# AMP.net
KiCad netlist of a schematic drawn in Altium Designer
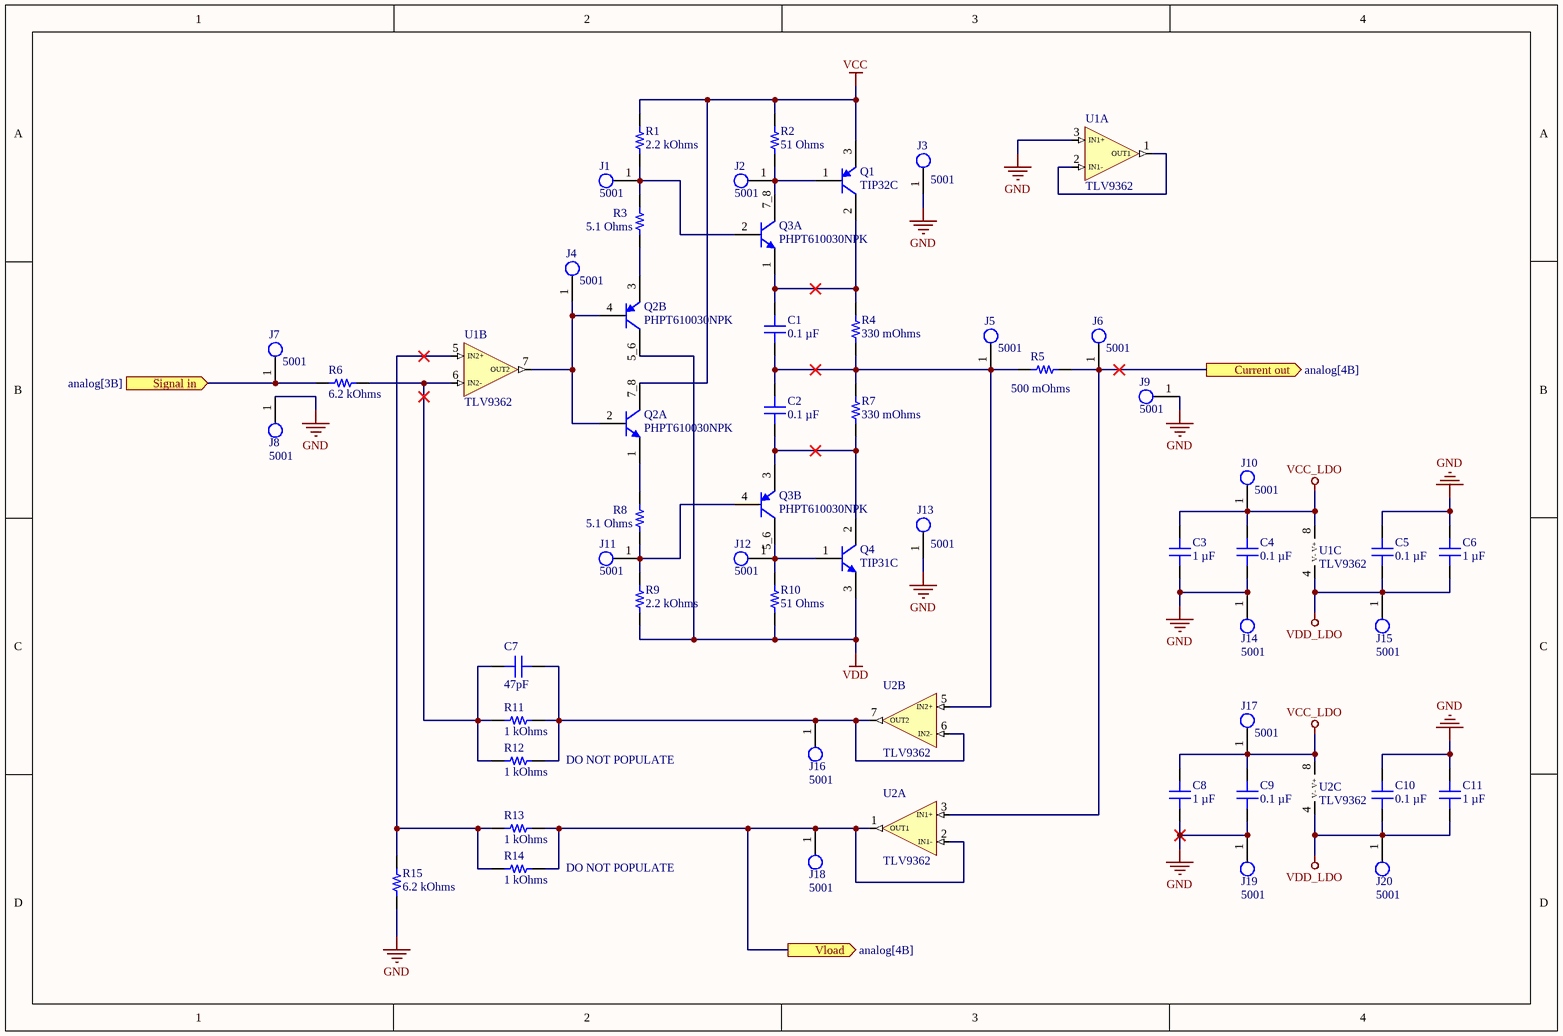
[diagram p0: AMP.SchDoc]

(export (version "E")
  (design (tool "Eeschema 10.0.6"))
  (components
    (comp (ref "C1")
      (value "0.1 µF")
      (footprint "CAP 1206_3216 - 0.8MM")
      (description "CAP CER 0.1UF 50V X7R 1206")
      (fields
        (field (name "PART NUMBER") "885012208087")
        (field (name "CAPACITANCE") "0.1 µF")
        (field (name "MANUFACTURER") "Würth Elektronik")
      )
      (libsource (lib "Celestial Altium Library - altium_library") (part "Capacitor"))
    )
    (comp (ref "C2")
      (value "0.1 µF")
      (footprint "CAP 1206_3216 - 0.8MM")
      (description "CAP CER 0.1UF 50V X7R 1206")
      (fields
        (field (name "PART NUMBER") "885012208087")
        (field (name "CAPACITANCE") "0.1 µF")
        (field (name "MANUFACTURER") "Würth Elektronik")
      )
      (libsource (lib "Celestial Altium Library - altium_library") (part "Capacitor"))
    )
    (comp (ref "C3")
      (value "1 µF")
      (footprint "CAP 1206_3216 - 0.8MM")
      (description "CAP CER 1UF 50V X7R 1206")
      (fields
        (field (name "PART NUMBER") "885012208093")
        (field (name "CAPACITANCE") "1 µF")
        (field (name "MANUFACTURER") "Würth Elektronik")
      )
      (libsource (lib "Celestial Altium Library - altium_library") (part "Capacitor"))
    )
    (comp (ref "C4")
      (value "0.1 µF")
      (footprint "CAP 1206_3216 - 0.8MM")
      (description "CAP CER 0.1UF 50V X7R 1206")
      (fields
        (field (name "PART NUMBER") "885012208087")
        (field (name "CAPACITANCE") "0.1 µF")
        (field (name "MANUFACTURER") "Würth Elektronik")
      )
      (libsource (lib "Celestial Altium Library - altium_library") (part "Capacitor"))
    )
    (comp (ref "C5")
      (value "0.1 µF")
      (footprint "CAP 1206_3216 - 0.8MM")
      (description "CAP CER 0.1UF 50V X7R 1206")
      (fields
        (field (name "PART NUMBER") "885012208087")
        (field (name "CAPACITANCE") "0.1 µF")
        (field (name "MANUFACTURER") "Würth Elektronik")
      )
      (libsource (lib "Celestial Altium Library - altium_library") (part "Capacitor"))
    )
    (comp (ref "C6")
      (value "1 µF")
      (footprint "CAP 1206_3216 - 0.8MM")
      (description "CAP CER 1UF 50V X7R 1206")
      (fields
        (field (name "PART NUMBER") "885012208093")
        (field (name "CAPACITANCE") "1 µF")
        (field (name "MANUFACTURER") "Würth Elektronik")
      )
      (libsource (lib "Celestial Altium Library - altium_library") (part "Capacitor"))
    )
    (comp (ref "C7")
      (value "47pF")
      (footprint "CAP 1206_3216 - 1.8MM")
      (description "CAP CER 47PF 1KV C0G/NP0 1206")
      (fields
        (field (name "PART NUMBER") "1206AA470KAT1A")
        (field (name "CAPACITANCE") "47pF")
        (field (name "MANUFACTURER") "AVX Corporation")
      )
      (libsource (lib "Celestial Altium Library - altium_library") (part "Capacitor"))
    )
    (comp (ref "C8")
      (value "1 µF")
      (footprint "CAP 1206_3216 - 0.8MM")
      (description "CAP CER 1UF 50V X7R 1206")
      (fields
        (field (name "PART NUMBER") "885012208093")
        (field (name "CAPACITANCE") "1 µF")
        (field (name "MANUFACTURER") "Würth Elektronik")
      )
      (libsource (lib "Celestial Altium Library - altium_library") (part "Capacitor"))
    )
    (comp (ref "C9")
      (value "0.1 µF")
      (footprint "CAP 1206_3216 - 0.8MM")
      (description "CAP CER 0.1UF 50V X7R 1206")
      (fields
        (field (name "PART NUMBER") "885012208087")
        (field (name "CAPACITANCE") "0.1 µF")
        (field (name "MANUFACTURER") "Würth Elektronik")
      )
      (libsource (lib "Celestial Altium Library - altium_library") (part "Capacitor"))
    )
    (comp (ref "C10")
      (value "0.1 µF")
      (footprint "CAP 1206_3216 - 0.8MM")
      (description "CAP CER 0.1UF 50V X7R 1206")
      (fields
        (field (name "PART NUMBER") "885012208087")
        (field (name "CAPACITANCE") "0.1 µF")
        (field (name "MANUFACTURER") "Würth Elektronik")
      )
      (libsource (lib "Celestial Altium Library - altium_library") (part "Capacitor"))
    )
    (comp (ref "C11")
      (value "1 µF")
      (footprint "CAP 1206_3216 - 0.8MM")
      (description "CAP CER 1UF 50V X7R 1206")
      (fields
        (field (name "PART NUMBER") "885012208093")
        (field (name "CAPACITANCE") "1 µF")
        (field (name "MANUFACTURER") "Würth Elektronik")
      )
      (libsource (lib "Celestial Altium Library - altium_library") (part "Capacitor"))
    )
    (comp (ref "J1")
      (value "5001")
      (footprint "FP-5001-MFG")
      (description "PC TEST POINT MINIATURE BLACK")
      (libsource (lib "za_koncar") (part "CMP-2000-05181-2"))
    )
    (comp (ref "J2")
      (value "5001")
      (footprint "FP-5001-MFG")
      (description "PC TEST POINT MINIATURE BLACK")
      (libsource (lib "za_koncar") (part "CMP-2000-05181-2"))
    )
    (comp (ref "J3")
      (value "5001")
      (footprint "FP-5001-MFG")
      (description "PC TEST POINT MINIATURE BLACK")
      (libsource (lib "za_koncar") (part "CMP-2000-05181-2"))
    )
    (comp (ref "J4")
      (value "5001")
      (footprint "FP-5001-MFG")
      (description "PC TEST POINT MINIATURE BLACK")
      (libsource (lib "za_koncar") (part "CMP-2000-05181-2"))
    )
    (comp (ref "J5")
      (value "5001")
      (footprint "FP-5001-MFG")
      (description "PC TEST POINT MINIATURE BLACK")
      (libsource (lib "za_koncar") (part "CMP-2000-05181-2"))
    )
    (comp (ref "J6")
      (value "5001")
      (footprint "FP-5001-MFG")
      (description "PC TEST POINT MINIATURE BLACK")
      (libsource (lib "za_koncar") (part "CMP-2000-05181-2"))
    )
    (comp (ref "J7")
      (value "5001")
      (footprint "FP-5001-MFG")
      (description "PC TEST POINT MINIATURE BLACK")
      (libsource (lib "za_koncar") (part "CMP-2000-05181-2"))
    )
    (comp (ref "J8")
      (value "5001")
      (footprint "FP-5001-MFG")
      (description "PC TEST POINT MINIATURE BLACK")
      (libsource (lib "za_koncar") (part "CMP-2000-05181-2"))
    )
    (comp (ref "J9")
      (value "5001")
      (footprint "FP-5001-MFG")
      (description "PC TEST POINT MINIATURE BLACK")
      (libsource (lib "za_koncar") (part "CMP-2000-05181-2"))
    )
    (comp (ref "J10")
      (value "5001")
      (footprint "FP-5001-MFG")
      (description "PC TEST POINT MINIATURE BLACK")
      (libsource (lib "za_koncar") (part "CMP-2000-05181-2"))
    )
    (comp (ref "J11")
      (value "5001")
      (footprint "FP-5001-MFG")
      (description "PC TEST POINT MINIATURE BLACK")
      (libsource (lib "za_koncar") (part "CMP-2000-05181-2"))
    )
    (comp (ref "J12")
      (value "5001")
      (footprint "FP-5001-MFG")
      (description "PC TEST POINT MINIATURE BLACK")
      (libsource (lib "za_koncar") (part "CMP-2000-05181-2"))
    )
    (comp (ref "J13")
      (value "5001")
      (footprint "FP-5001-MFG")
      (description "PC TEST POINT MINIATURE BLACK")
      (libsource (lib "za_koncar") (part "CMP-2000-05181-2"))
    )
    (comp (ref "J14")
      (value "5001")
      (footprint "FP-5001-MFG")
      (description "PC TEST POINT MINIATURE BLACK")
      (libsource (lib "za_koncar") (part "CMP-2000-05181-2"))
    )
    (comp (ref "J15")
      (value "5001")
      (footprint "FP-5001-MFG")
      (description "PC TEST POINT MINIATURE BLACK")
      (libsource (lib "za_koncar") (part "CMP-2000-05181-2"))
    )
    (comp (ref "J16")
      (value "5001")
      (footprint "FP-5001-MFG")
      (description "PC TEST POINT MINIATURE BLACK")
      (libsource (lib "za_koncar") (part "CMP-2000-05181-2"))
    )
    (comp (ref "J17")
      (value "5001")
      (footprint "FP-5001-MFG")
      (description "PC TEST POINT MINIATURE BLACK")
      (libsource (lib "za_koncar") (part "CMP-2000-05181-2"))
    )
    (comp (ref "J18")
      (value "5001")
      (footprint "FP-5001-MFG")
      (description "PC TEST POINT MINIATURE BLACK")
      (libsource (lib "za_koncar") (part "CMP-2000-05181-2"))
    )
    (comp (ref "J19")
      (value "5001")
      (footprint "FP-5001-MFG")
      (description "PC TEST POINT MINIATURE BLACK")
      (libsource (lib "za_koncar") (part "CMP-2000-05181-2"))
    )
    (comp (ref "J20")
      (value "5001")
      (footprint "FP-5001-MFG")
      (description "PC TEST POINT MINIATURE BLACK")
      (libsource (lib "za_koncar") (part "CMP-2000-05181-2"))
    )
    (comp (ref "Q1")
      (value "TIP32C")
      (footprint "ONSC-TO-220-3-221A-09")
      (description "Complementary Silicon Plastic Power Transistor, 3-Pin TO-220, Tube")
      (fields (field (name "MANUFACTURER") "On Semiconductor"))
      (libsource (lib "ON Semi General Purpose Transistors") (part "TIP32C"))
    )
    (comp (ref "Q2")
      (value "PHPT610030NPK")
      (footprint "TRANS_BUK9K18-40E,115")
      (libsource (lib "za_koncar") (part "PHPT610030NPK"))
    )
    (comp (ref "Q3")
      (value "PHPT610030NPK")
      (footprint "TRANS_BUK9K18-40E,115")
      (libsource (lib "za_koncar") (part "PHPT610030NPK"))
    )
    (comp (ref "Q4")
      (value "TIP31C")
      (footprint "ONSC-TO-220-3-221A-09")
      (description "Complementary Silicon Plastic Power Transistor, 3-Pin TO-220, Tube")
      (fields (field (name "MANUFACTURER") "On Semiconductor"))
      (libsource (lib "ON Semi General Purpose Transistors") (part "TIP31C"))
    )
    (comp (ref "R1")
      (value "2.2 kOhms")
      (footprint "RES 1206_3216")
      (description "RES SMD 2.2K OHM 5% 1/4W 1206")
      (fields
        (field (name "PART NUMBER") "ERJ-8GEYJ222V")
        (field (name "MANUFACTURER") "Panasonic Electronic Components")
      )
      (libsource (lib "Celestial Altium Library - altium_library") (part "Resistor"))
    )
    (comp (ref "R2")
      (value "51 Ohms")
      (footprint "RES 1206_3216")
      (description "RES SMD 51 OHM 5% 1/4W 1206")
      (fields
        (field (name "PART NUMBER") "ERJ-8GEYJ510V")
        (field (name "MANUFACTURER") "Panasonic Electronic Components")
      )
      (libsource (lib "Celestial Altium Library - altium_library") (part "Resistor"))
    )
    (comp (ref "R3")
      (value "5.1 Ohms")
      (footprint "RES 1206_3216")
      (description "RES SMD 5.1 OHM 5% 1/4W 1206")
      (fields
        (field (name "PART NUMBER") "ERJ-8GEYJ5R1V")
        (field (name "MANUFACTURER") "Panasonic Electronic Components")
      )
      (libsource (lib "Celestial Altium Library - altium_library") (part "Resistor"))
    )
    (comp (ref "R4")
      (value "330 mOhms")
      (footprint "STACKPOLE CSR2512")
      (description "RES 0.33 OHM 1% 2W 2512")
      (fields
        (field (name "PART NUMBER") "CSRN2512FKR330")
        (field (name "MANUFACTURER") "Stackpole Electronics Inc")
      )
      (libsource (lib "Celestial Altium Library - altium_library") (part "Resistor"))
    )
    (comp (ref "R5")
      (value "500 mOhms")
      (footprint "STACKPOLE CSR2512")
      (description "RES 0.5 OHM 1% 2W 2512")
      (fields
        (field (name "PART NUMBER") "CSRN2512FKR500")
        (field (name "MANUFACTURER") "Stackpole Electronics Inc")
      )
      (libsource (lib "Celestial Altium Library - altium_library") (part "Resistor"))
    )
    (comp (ref "R6")
      (value "6.2 kOhms")
      (footprint "RES 1206_3216")
      (description "RES SMD 6.2K OHM 0.1% 1/4W 1206")
      (fields
        (field (name "PART NUMBER") "ERA-8AEB622V")
        (field (name "MANUFACTURER") "Panasonic Electronic Components")
      )
      (libsource (lib "Celestial Altium Library - altium_library") (part "Resistor"))
    )
    (comp (ref "R7")
      (value "330 mOhms")
      (footprint "STACKPOLE CSR2512")
      (description "RES 0.33 OHM 1% 2W 2512")
      (fields
        (field (name "PART NUMBER") "CSRN2512FKR330")
        (field (name "MANUFACTURER") "Stackpole Electronics Inc")
      )
      (libsource (lib "Celestial Altium Library - altium_library") (part "Resistor"))
    )
    (comp (ref "R8")
      (value "5.1 Ohms")
      (footprint "RES 1206_3216")
      (description "RES SMD 5.1 OHM 5% 1/4W 1206")
      (fields
        (field (name "PART NUMBER") "ERJ-8GEYJ5R1V")
        (field (name "MANUFACTURER") "Panasonic Electronic Components")
      )
      (libsource (lib "Celestial Altium Library - altium_library") (part "Resistor"))
    )
    (comp (ref "R9")
      (value "2.2 kOhms")
      (footprint "RES 1206_3216")
      (description "RES SMD 2.2K OHM 5% 1/4W 1206")
      (fields
        (field (name "PART NUMBER") "ERJ-8GEYJ222V")
        (field (name "MANUFACTURER") "Panasonic Electronic Components")
      )
      (libsource (lib "Celestial Altium Library - altium_library") (part "Resistor"))
    )
    (comp (ref "R10")
      (value "51 Ohms")
      (footprint "RES 1206_3216")
      (description "RES SMD 51 OHM 5% 1/4W 1206")
      (fields
        (field (name "PART NUMBER") "ERJ-8GEYJ510V")
        (field (name "MANUFACTURER") "Panasonic Electronic Components")
      )
      (libsource (lib "Celestial Altium Library - altium_library") (part "Resistor"))
    )
    (comp (ref "R11")
      (value "1 kOhms")
      (footprint "RES 1206_3216")
      (description "RES SMD 1K OHM 0.1% 1/4W 1206")
      (fields
        (field (name "PART NUMBER") "ERA-8AEB102V")
        (field (name "MANUFACTURER") "Panasonic Electronic Components")
      )
      (libsource (lib "Celestial Altium Library - altium_library") (part "Resistor"))
    )
    (comp (ref "R12")
      (value "1 kOhms")
      (footprint "RES 1206_3216")
      (description "RES SMD 1K OHM 0.1% 1/4W 1206")
      (fields
        (field (name "PART NUMBER") "ERA-8AEB102V")
        (field (name "MANUFACTURER") "Panasonic Electronic Components")
      )
      (libsource (lib "Celestial Altium Library - altium_library") (part "Resistor"))
    )
    (comp (ref "R13")
      (value "1 kOhms")
      (footprint "RES 1206_3216")
      (description "RES SMD 1K OHM 0.1% 1/4W 1206")
      (fields
        (field (name "PART NUMBER") "ERA-8AEB102V")
        (field (name "MANUFACTURER") "Panasonic Electronic Components")
      )
      (libsource (lib "Celestial Altium Library - altium_library") (part "Resistor"))
    )
    (comp (ref "R14")
      (value "1 kOhms")
      (footprint "RES 1206_3216")
      (description "RES SMD 1K OHM 0.1% 1/4W 1206")
      (fields
        (field (name "PART NUMBER") "ERA-8AEB102V")
        (field (name "MANUFACTURER") "Panasonic Electronic Components")
      )
      (libsource (lib "Celestial Altium Library - altium_library") (part "Resistor"))
    )
    (comp (ref "R15")
      (value "6.2 kOhms")
      (footprint "RES 1206_3216")
      (description "RES SMD 6.2K OHM 0.1% 1/4W 1206")
      (fields
        (field (name "PART NUMBER") "ERA-8AEB622V")
        (field (name "MANUFACTURER") "Panasonic Electronic Components")
      )
      (libsource (lib "Celestial Altium Library - altium_library") (part "Resistor"))
    )
    (comp (ref "U1")
      (value "TLV9362")
      (footprint "za_koncar:SOIC8-127P600X175-8N")
      (description "TLV936x 10-MHz, 40-V, RRO, Operational Amplifie")
      (libsource (lib "za_koncar") (part "TLV9362"))
    )
    (comp (ref "U2")
      (value "TLV9362")
      (footprint "za_koncar:SOIC8-127P600X175-8N")
      (description "TLV936x 10-MHz, 40-V, RRO, Operational Amplifie")
      (libsource (lib "za_koncar") (part "TLV9362"))
    )
  )
  (nets
    (net (code "1") (name "/Current out") (class "Default")
      (node (ref "J6") (pin "1") (pinfunction "1_1") (pintype "passive"))
      (node (ref "R5") (pin "1") (pinfunction "1_1") (pintype "passive"))
      (node (ref "U2") (pin "3") (pinfunction "IN1+_3") (pintype "input"))
    )
    (net (code "2") (name "/Signal in") (class "Default")
      (node (ref "J7") (pin "1") (pinfunction "1_1") (pintype "passive"))
      (node (ref "R6") (pin "2") (pinfunction "2_2") (pintype "passive"))
    )
    (net (code "3") (name "/Vload") (class "Default")
      (node (ref "J18") (pin "1") (pinfunction "1_1") (pintype "passive"))
      (node (ref "R13") (pin "2") (pinfunction "2_2") (pintype "passive"))
      (node (ref "R14") (pin "2") (pinfunction "2_2") (pintype "passive"))
      (node (ref "U2") (pin "1") (pinfunction "OUT1_1") (pintype "output"))
      (node (ref "U2") (pin "2") (pinfunction "IN1-_2") (pintype "input"))
    )
    (net (code "4") (name "GND") (class "Default")
      (node (ref "C10") (pin "2") (pinfunction "2_2") (pintype "passive"))
      (node (ref "C11") (pin "2") (pinfunction "2_2") (pintype "passive"))
      (node (ref "C3") (pin "1") (pinfunction "1_1") (pintype "passive"))
      (node (ref "C4") (pin "1") (pinfunction "1_1") (pintype "passive"))
      (node (ref "C5") (pin "2") (pinfunction "2_2") (pintype "passive"))
      (node (ref "C6") (pin "2") (pinfunction "2_2") (pintype "passive"))
      (node (ref "C8") (pin "1") (pinfunction "1_1") (pintype "passive"))
      (node (ref "C9") (pin "1") (pinfunction "1_1") (pintype "passive"))
      (node (ref "J13") (pin "1") (pinfunction "1_1") (pintype "passive"))
      (node (ref "J14") (pin "1") (pinfunction "1_1") (pintype "passive"))
      (node (ref "J19") (pin "1") (pinfunction "1_1") (pintype "passive"))
      (node (ref "J3") (pin "1") (pinfunction "1_1") (pintype "passive"))
      (node (ref "J8") (pin "1") (pinfunction "1_1") (pintype "passive"))
      (node (ref "J9") (pin "1") (pinfunction "1_1") (pintype "passive"))
      (node (ref "R15") (pin "1") (pinfunction "1_1") (pintype "passive"))
      (node (ref "U1") (pin "3") (pinfunction "IN1+_3") (pintype "input"))
    )
    (net (code "5") (name "Net-(Q1-B)") (class "Default")
      (node (ref "J2") (pin "1") (pinfunction "1_1") (pintype "passive"))
      (node (ref "Q1") (pin "1") (pinfunction "B_1") (pintype "passive"))
      (node (ref "Q3") (pin "7_8") (pinfunction "C1_7_8") (pintype "passive"))
      (node (ref "R2") (pin "1") (pinfunction "1_1") (pintype "passive"))
    )
    (net (code "6") (name "Net-(Q1-C)") (class "Default")
      (node (ref "C1") (pin "2") (pinfunction "2_2") (pintype "passive"))
      (node (ref "Q1") (pin "2") (pinfunction "C_2") (pintype "passive"))
      (node (ref "Q3") (pin "1") (pinfunction "E1_1") (pintype "passive"))
      (node (ref "R4") (pin "2") (pinfunction "2_2") (pintype "passive"))
    )
    (net (code "7") (name "Net-(Q2A-B1)") (class "Default")
      (node (ref "J4") (pin "1") (pinfunction "1_1") (pintype "passive"))
      (node (ref "Q2") (pin "2") (pinfunction "B1_2") (pintype "passive"))
      (node (ref "Q2") (pin "4") (pinfunction "B2_4") (pintype "passive"))
      (node (ref "U1") (pin "7") (pinfunction "OUT2_7") (pintype "output"))
    )
    (net (code "8") (name "Net-(Q2A-E1)") (class "Default")
      (node (ref "Q2") (pin "1") (pinfunction "E1_1") (pintype "passive"))
      (node (ref "R8") (pin "2") (pinfunction "2_2") (pintype "passive"))
    )
    (net (code "9") (name "Net-(Q2B-E2)") (class "Default")
      (node (ref "Q2") (pin "3") (pinfunction "E2_3") (pintype "passive"))
      (node (ref "R3") (pin "1") (pinfunction "1_1") (pintype "passive"))
    )
    (net (code "10") (name "Net-(Q3A-B1)") (class "Default")
      (node (ref "J1") (pin "1") (pinfunction "1_1") (pintype "passive"))
      (node (ref "Q3") (pin "2") (pinfunction "B1_2") (pintype "passive"))
      (node (ref "R1") (pin "1") (pinfunction "1_1") (pintype "passive"))
      (node (ref "R3") (pin "2") (pinfunction "2_2") (pintype "passive"))
    )
    (net (code "11") (name "Net-(Q3B-B2)") (class "Default")
      (node (ref "J11") (pin "1") (pinfunction "1_1") (pintype "passive"))
      (node (ref "Q3") (pin "4") (pinfunction "B2_4") (pintype "passive"))
      (node (ref "R8") (pin "1") (pinfunction "1_1") (pintype "passive"))
      (node (ref "R9") (pin "2") (pinfunction "2_2") (pintype "passive"))
    )
    (net (code "12") (name "Net-(Q3B-C2)") (class "Default")
      (node (ref "J12") (pin "1") (pinfunction "1_1") (pintype "passive"))
      (node (ref "Q3") (pin "5_6") (pinfunction "C2_5_6") (pintype "passive"))
      (node (ref "Q4") (pin "1") (pinfunction "B_1") (pintype "passive"))
      (node (ref "R10") (pin "2") (pinfunction "2_2") (pintype "passive"))
    )
    (net (code "13") (name "Net-(Q3B-E2)") (class "Default")
      (node (ref "C2") (pin "1") (pinfunction "1_1") (pintype "passive"))
      (node (ref "Q3") (pin "3") (pinfunction "E2_3") (pintype "passive"))
      (node (ref "Q4") (pin "2") (pinfunction "C_2") (pintype "passive"))
      (node (ref "R7") (pin "1") (pinfunction "1_1") (pintype "passive"))
    )
    (net (code "14") (name "Net-(U1A-IN1-)") (class "Default")
      (node (ref "U1") (pin "1") (pinfunction "OUT1_1") (pintype "output"))
      (node (ref "U1") (pin "2") (pinfunction "IN1-_2") (pintype "input"))
    )
    (net (code "15") (name "Net-(U1B-IN2+)") (class "Default")
      (node (ref "R13") (pin "1") (pinfunction "1_1") (pintype "passive"))
      (node (ref "R14") (pin "1") (pinfunction "1_1") (pintype "passive"))
      (node (ref "R15") (pin "2") (pinfunction "2_2") (pintype "passive"))
      (node (ref "U1") (pin "5") (pinfunction "IN2+_5") (pintype "input"))
    )
    (net (code "16") (name "Net-(U1B-IN2-)") (class "Default")
      (node (ref "C7") (pin "1") (pinfunction "1_1") (pintype "passive"))
      (node (ref "R11") (pin "1") (pinfunction "1_1") (pintype "passive"))
      (node (ref "R12") (pin "1") (pinfunction "1_1") (pintype "passive"))
      (node (ref "R6") (pin "1") (pinfunction "1_1") (pintype "passive"))
      (node (ref "U1") (pin "6") (pinfunction "IN2-_6") (pintype "input"))
    )
    (net (code "17") (name "Net-(U2B-IN2+)") (class "Default")
      (node (ref "C1") (pin "1") (pinfunction "1_1") (pintype "passive"))
      (node (ref "C2") (pin "2") (pinfunction "2_2") (pintype "passive"))
      (node (ref "J5") (pin "1") (pinfunction "1_1") (pintype "passive"))
      (node (ref "R4") (pin "1") (pinfunction "1_1") (pintype "passive"))
      (node (ref "R5") (pin "2") (pinfunction "2_2") (pintype "passive"))
      (node (ref "R7") (pin "2") (pinfunction "2_2") (pintype "passive"))
      (node (ref "U2") (pin "5") (pinfunction "IN2+_5") (pintype "input"))
    )
    (net (code "18") (name "Net-(U2B-IN2-)") (class "Default")
      (node (ref "C7") (pin "2") (pinfunction "2_2") (pintype "passive"))
      (node (ref "J16") (pin "1") (pinfunction "1_1") (pintype "passive"))
      (node (ref "R11") (pin "2") (pinfunction "2_2") (pintype "passive"))
      (node (ref "R12") (pin "2") (pinfunction "2_2") (pintype "passive"))
      (node (ref "U2") (pin "6") (pinfunction "IN2-_6") (pintype "input"))
      (node (ref "U2") (pin "7") (pinfunction "OUT2_7") (pintype "output"))
    )
    (net (code "19") (name "VCC") (class "Default")
      (node (ref "Q1") (pin "3") (pinfunction "E_3") (pintype "passive"))
      (node (ref "Q2") (pin "7_8") (pinfunction "C1_7_8") (pintype "passive"))
      (node (ref "R1") (pin "2") (pinfunction "2_2") (pintype "passive"))
      (node (ref "R2") (pin "2") (pinfunction "2_2") (pintype "passive"))
    )
    (net (code "20") (name "VCC_LDO") (class "Default")
      (node (ref "C3") (pin "2") (pinfunction "2_2") (pintype "passive"))
      (node (ref "C4") (pin "2") (pinfunction "2_2") (pintype "passive"))
      (node (ref "C8") (pin "2") (pinfunction "2_2") (pintype "passive"))
      (node (ref "C9") (pin "2") (pinfunction "2_2") (pintype "passive"))
      (node (ref "J10") (pin "1") (pinfunction "1_1") (pintype "passive"))
      (node (ref "J17") (pin "1") (pinfunction "1_1") (pintype "passive"))
      (node (ref "U1") (pin "8") (pinfunction "V+_8") (pintype "power_in"))
      (node (ref "U2") (pin "8") (pinfunction "V+_8") (pintype "power_in"))
    )
    (net (code "21") (name "VDD") (class "Default")
      (node (ref "Q2") (pin "5_6") (pinfunction "C2_5_6") (pintype "passive"))
      (node (ref "Q4") (pin "3") (pinfunction "E_3") (pintype "passive"))
      (node (ref "R10") (pin "1") (pinfunction "1_1") (pintype "passive"))
      (node (ref "R9") (pin "1") (pinfunction "1_1") (pintype "passive"))
    )
    (net (code "22") (name "VDD_LDO") (class "Default")
      (node (ref "C10") (pin "1") (pinfunction "1_1") (pintype "passive"))
      (node (ref "C11") (pin "1") (pinfunction "1_1") (pintype "passive"))
      (node (ref "C5") (pin "1") (pinfunction "1_1") (pintype "passive"))
      (node (ref "C6") (pin "1") (pinfunction "1_1") (pintype "passive"))
      (node (ref "J15") (pin "1") (pinfunction "1_1") (pintype "passive"))
      (node (ref "J20") (pin "1") (pinfunction "1_1") (pintype "passive"))
      (node (ref "U1") (pin "4") (pinfunction "V-_4") (pintype "power_in"))
      (node (ref "U2") (pin "4") (pinfunction "V-_4") (pintype "power_in"))
    )
  )
)
